# uart.net
KiCad netlist of a schematic drawn in Altium Designer
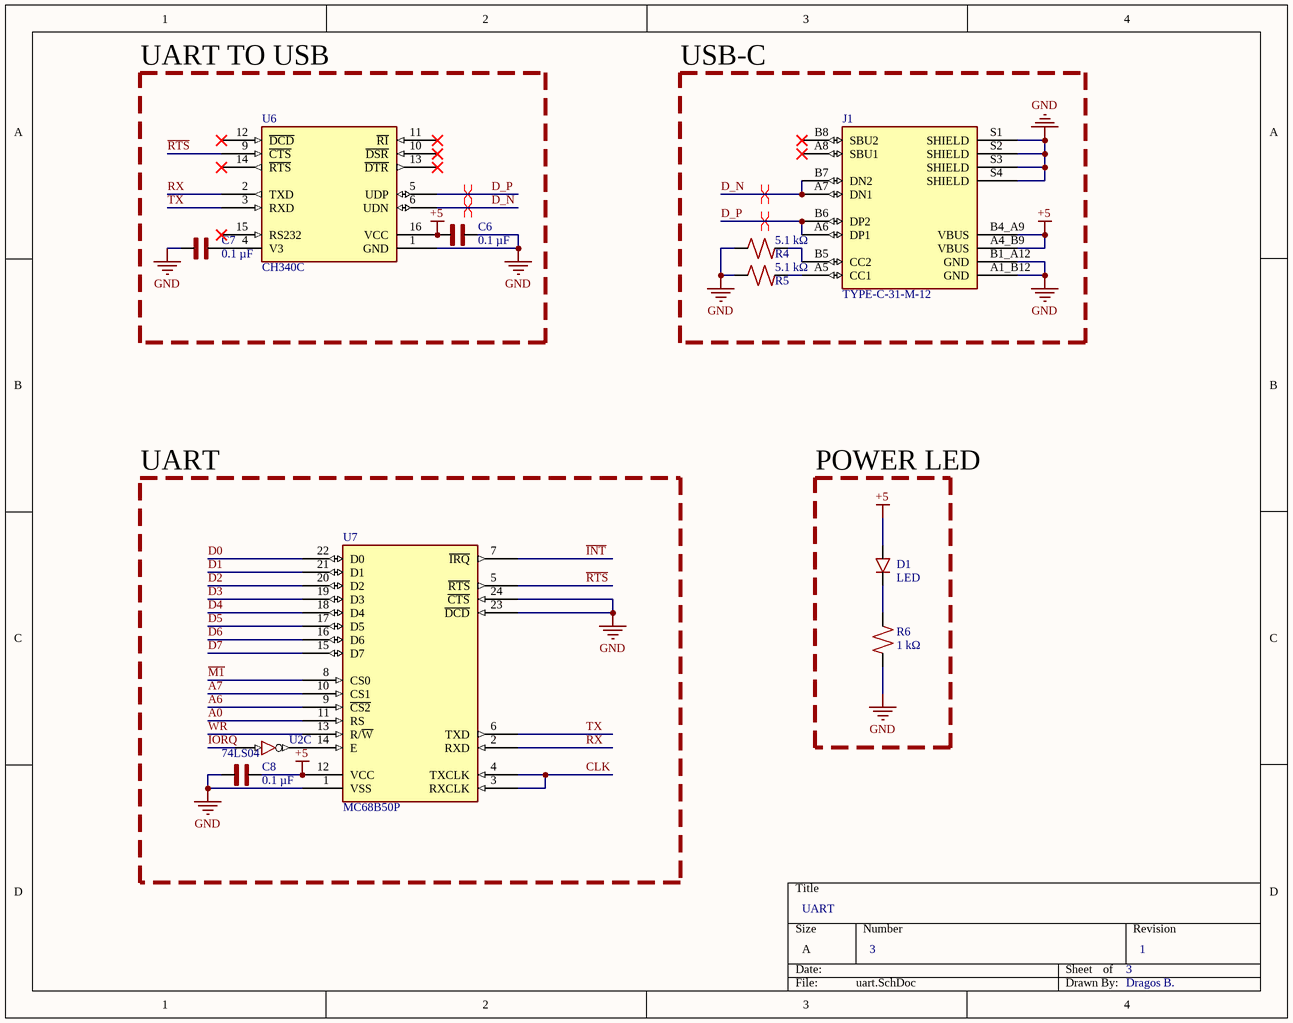
[diagram p0: uart.SchDoc]

(export (version "E")
  (design (tool "Eeschema 10.0.6"))
  (components
    (comp (ref "C6")
      (value "0.1 µF")
      (footprint "Capacitor")
      (fields (field (name "MP") "ECWFG70105K") (field (name "MF") "Panasonic"))
      (libsource (lib "components") (part "CAPACITOR"))
    )
    (comp (ref "C7")
      (value "0.1 µF")
      (footprint "Capacitor")
      (fields (field (name "MP") "ECWFG70105K") (field (name "MF") "Panasonic"))
      (libsource (lib "components") (part "CAPACITOR"))
    )
    (comp (ref "C8")
      (value "0.1 µF")
      (footprint "Capacitor")
      (fields (field (name "MP") "ECWFG70105K") (field (name "MF") "Panasonic"))
      (libsource (lib "components") (part "CAPACITOR"))
    )
    (comp (ref "D1") (value "LED") (footprint "DIODE") (libsource (lib "components") (part "LED")))
    (comp (ref "J1")
      (value "TYPE-C-31-M-12")
      (footprint "HRO_TYPE-C-31-M-12")
      (fields (field (name "MF") "HRO Electronics Co., Ltd."))
      (libsource (lib "components") (part "TYPE-C-31-M-12"))
    )
    (comp (ref "R4")
      (value "5.1 kΩ")
      (footprint "Axial 0.4")
      (fields (field (name "MP") "ERJU01J131C"))
      (libsource (lib "components") (part "RESISTOR"))
    )
    (comp (ref "R5")
      (value "5.1 kΩ")
      (footprint "Axial 0.4")
      (fields (field (name "MP") "ERJU01J131C"))
      (libsource (lib "components") (part "RESISTOR"))
    )
    (comp (ref "R6")
      (value "1 kΩ")
      (footprint "Axial 0.4")
      (fields (field (name "MP") "ERJU01J131C"))
      (libsource (lib "components") (part "RESISTOR"))
    )
    (comp (ref "U2")
      (value "74LS04")
      (footprint "DIP14")
      (description "Hex Inverters")
      (libsource (lib "components") (part "74LS04"))
    )
    (comp (ref "U6")
      (value "CH340C")
      (footprint "SOP127P600X175-16M")
      (libsource (lib "components") (part "CH340C"))
    )
    (comp (ref "U7") (value "MC68B50P") (footprint "DIP24") (libsource (lib "components") (part "MC68B50P")))
  )
  (nets
    (net (code "1") (name "+5") (class "Default")
      (node (ref "C6") (pin "2") (pinfunction "2_2") (pintype "passive"))
      (node (ref "C8") (pin "1") (pinfunction "1_1") (pintype "passive"))
      (node (ref "D1") (pin "A") (pinfunction "A_A") (pintype "passive"))
      (node (ref "J1") (pin "A4_B9") (pinfunction "VBUS_A4_B9") (pintype "power_in"))
      (node (ref "J1") (pin "B4_A9") (pinfunction "VBUS_B4_A9") (pintype "power_in"))
      (node (ref "U6") (pin "16") (pinfunction "VCC_16") (pintype "power_in"))
      (node (ref "U7") (pin "12") (pinfunction "VCC_12") (pintype "power_in"))
    )
    (net (code "2") (name "/A0") (class "Default")
      (node (ref "U7") (pin "11") (pinfunction "RS_11") (pintype "input"))
    )
    (net (code "3") (name "/A6") (class "Default")
      (node (ref "U7") (pin "9") (pinfunction "CS2_9") (pintype "input"))
    )
    (net (code "4") (name "/A7") (class "Default")
      (node (ref "U7") (pin "10") (pinfunction "CS1_10") (pintype "input"))
    )
    (net (code "5") (name "/CLK") (class "Default")
      (node (ref "U7") (pin "3") (pinfunction "RXCLK_3") (pintype "input"))
      (node (ref "U7") (pin "4") (pinfunction "TXCLK_4") (pintype "input"))
    )
    (net (code "6") (name "/D0") (class "Default")
      (node (ref "U7") (pin "22") (pinfunction "D0_22") (pintype "bidirectional"))
    )
    (net (code "7") (name "/D1") (class "Default")
      (node (ref "U7") (pin "21") (pinfunction "D1_21") (pintype "bidirectional"))
    )
    (net (code "8") (name "/D2") (class "Default")
      (node (ref "U7") (pin "20") (pinfunction "D2_20") (pintype "bidirectional"))
    )
    (net (code "9") (name "/D3") (class "Default")
      (node (ref "U7") (pin "19") (pinfunction "D3_19") (pintype "bidirectional"))
    )
    (net (code "10") (name "/D4") (class "Default")
      (node (ref "U7") (pin "18") (pinfunction "D4_18") (pintype "bidirectional"))
    )
    (net (code "11") (name "/D5") (class "Default")
      (node (ref "U7") (pin "17") (pinfunction "D5_17") (pintype "bidirectional"))
    )
    (net (code "12") (name "/D6") (class "Default")
      (node (ref "U7") (pin "16") (pinfunction "D6_16") (pintype "bidirectional"))
    )
    (net (code "13") (name "/D7") (class "Default")
      (node (ref "U7") (pin "15") (pinfunction "D7_15") (pintype "bidirectional"))
    )
    (net (code "14") (name "/D_N") (class "Default")
      (node (ref "J1") (pin "A7") (pinfunction "DN1_A7") (pintype "bidirectional"))
      (node (ref "J1") (pin "B7") (pinfunction "DN2_B7") (pintype "bidirectional"))
      (node (ref "U6") (pin "6") (pinfunction "UDN_6") (pintype "bidirectional"))
    )
    (net (code "15") (name "/D_P") (class "Default")
      (node (ref "J1") (pin "A6") (pinfunction "DP1_A6") (pintype "bidirectional"))
      (node (ref "J1") (pin "B6") (pinfunction "DP2_B6") (pintype "bidirectional"))
      (node (ref "U6") (pin "5") (pinfunction "UDP_5") (pintype "bidirectional"))
    )
    (net (code "16") (name "/INT") (class "Default")
      (node (ref "U7") (pin "7") (pinfunction "IRQ_7") (pintype "output"))
    )
    (net (code "17") (name "/IORQ") (class "Default")
      (node (ref "U2") (pin "5") (pinfunction "A3_5") (pintype "input"))
    )
    (net (code "18") (name "/M1") (class "Default")
      (node (ref "U7") (pin "8") (pinfunction "CS0_8") (pintype "input"))
    )
    (net (code "19") (name "/RTS") (class "Default")
      (node (ref "U6") (pin "9") (pinfunction "CTS_9") (pintype "input"))
      (node (ref "U7") (pin "5") (pinfunction "RTS_5") (pintype "output"))
    )
    (net (code "20") (name "/RX") (class "Default")
      (node (ref "U6") (pin "2") (pinfunction "TXD_2") (pintype "output"))
      (node (ref "U7") (pin "2") (pinfunction "RXD_2") (pintype "input"))
    )
    (net (code "21") (name "/TX") (class "Default")
      (node (ref "U6") (pin "3") (pinfunction "RXD_3") (pintype "input"))
      (node (ref "U7") (pin "6") (pinfunction "TXD_6") (pintype "output"))
    )
    (net (code "22") (name "/WR") (class "Default")
      (node (ref "U7") (pin "13") (pinfunction "R/~{W}_13") (pintype "input"))
    )
    (net (code "23") (name "GND") (class "Default")
      (node (ref "C6") (pin "1") (pinfunction "1_1") (pintype "passive"))
      (node (ref "C7") (pin "2") (pinfunction "2_2") (pintype "passive"))
      (node (ref "C8") (pin "2") (pinfunction "2_2") (pintype "passive"))
      (node (ref "J1") (pin "A1_B12") (pinfunction "GND_A1_B12") (pintype "power_in"))
      (node (ref "J1") (pin "B1_A12") (pinfunction "GND_B1_A12") (pintype "power_in"))
      (node (ref "J1") (pin "S1") (pinfunction "SHIELD_S1") (pintype "passive"))
      (node (ref "J1") (pin "S2") (pinfunction "SHIELD_S2") (pintype "passive"))
      (node (ref "J1") (pin "S3") (pinfunction "SHIELD_S3") (pintype "passive"))
      (node (ref "J1") (pin "S4") (pinfunction "SHIELD_S4") (pintype "passive"))
      (node (ref "R4") (pin "1") (pinfunction "1_1") (pintype "passive"))
      (node (ref "R5") (pin "1") (pinfunction "1_1") (pintype "passive"))
      (node (ref "R6") (pin "1") (pinfunction "1_1") (pintype "passive"))
      (node (ref "U6") (pin "1") (pinfunction "GND_1") (pintype "power_in"))
      (node (ref "U7") (pin "1") (pinfunction "VSS_1") (pintype "power_in"))
      (node (ref "U7") (pin "23") (pinfunction "DCD_23") (pintype "input"))
      (node (ref "U7") (pin "24") (pinfunction "CTS_24") (pintype "input"))
    )
    (net (code "24") (name "Net-(D1-PadK)") (class "Default")
      (node (ref "D1") (pin "K") (pinfunction "K_K") (pintype "passive"))
      (node (ref "R6") (pin "2") (pinfunction "2_2") (pintype "passive"))
    )
    (net (code "25") (name "Net-(J1-CC1)") (class "Default")
      (node (ref "J1") (pin "A5") (pinfunction "CC1_A5") (pintype "bidirectional"))
      (node (ref "R5") (pin "2") (pinfunction "2_2") (pintype "passive"))
    )
    (net (code "26") (name "Net-(J1-CC2)") (class "Default")
      (node (ref "J1") (pin "B5") (pinfunction "CC2_B5") (pintype "bidirectional"))
      (node (ref "R4") (pin "2") (pinfunction "2_2") (pintype "passive"))
    )
    (net (code "27") (name "Net-(U2C-Y3)") (class "Default")
      (node (ref "U2") (pin "6") (pinfunction "Y3_6") (pintype "output"))
      (node (ref "U7") (pin "14") (pinfunction "E_14") (pintype "input"))
    )
    (net (code "28") (name "Net-(U6-V3)") (class "Default")
      (node (ref "C7") (pin "1") (pinfunction "1_1") (pintype "passive"))
      (node (ref "U6") (pin "4") (pinfunction "V3_4") (pintype "power_in"))
    )
    (net (code "29") (name "unconnected-(J1-SBU1-PadA8)") (class "Default")
      (node (ref "J1") (pin "A8") (pinfunction "SBU1_A8") (pintype "bidirectional+no_connect"))
    )
    (net (code "30") (name "unconnected-(J1-SBU2-PadB8)") (class "Default")
      (node (ref "J1") (pin "B8") (pinfunction "SBU2_B8") (pintype "bidirectional+no_connect"))
    )
    (net (code "31") (name "unconnected-(U6-DCD-Pad12)") (class "Default")
      (node (ref "U6") (pin "12") (pinfunction "DCD_12") (pintype "input+no_connect"))
    )
    (net (code "32") (name "unconnected-(U6-DSR-Pad10)") (class "Default")
      (node (ref "U6") (pin "10") (pinfunction "DSR_10") (pintype "input+no_connect"))
    )
    (net (code "33") (name "unconnected-(U6-DTR-Pad13)") (class "Default")
      (node (ref "U6") (pin "13") (pinfunction "DTR_13") (pintype "output+no_connect"))
    )
    (net (code "34") (name "unconnected-(U6-RI-Pad11)") (class "Default")
      (node (ref "U6") (pin "11") (pinfunction "RI_11") (pintype "input+no_connect"))
    )
    (net (code "35") (name "unconnected-(U6-RS232-Pad15)") (class "Default")
      (node (ref "U6") (pin "15") (pinfunction "RS232_15") (pintype "input+no_connect"))
    )
    (net (code "36") (name "unconnected-(U6-RTS-Pad14)") (class "Default")
      (node (ref "U6") (pin "14") (pinfunction "RTS_14") (pintype "output+no_connect"))
    )
  )
)
